# x49_dash.net
KiCad netlist of a schematic drawn in EAGLE
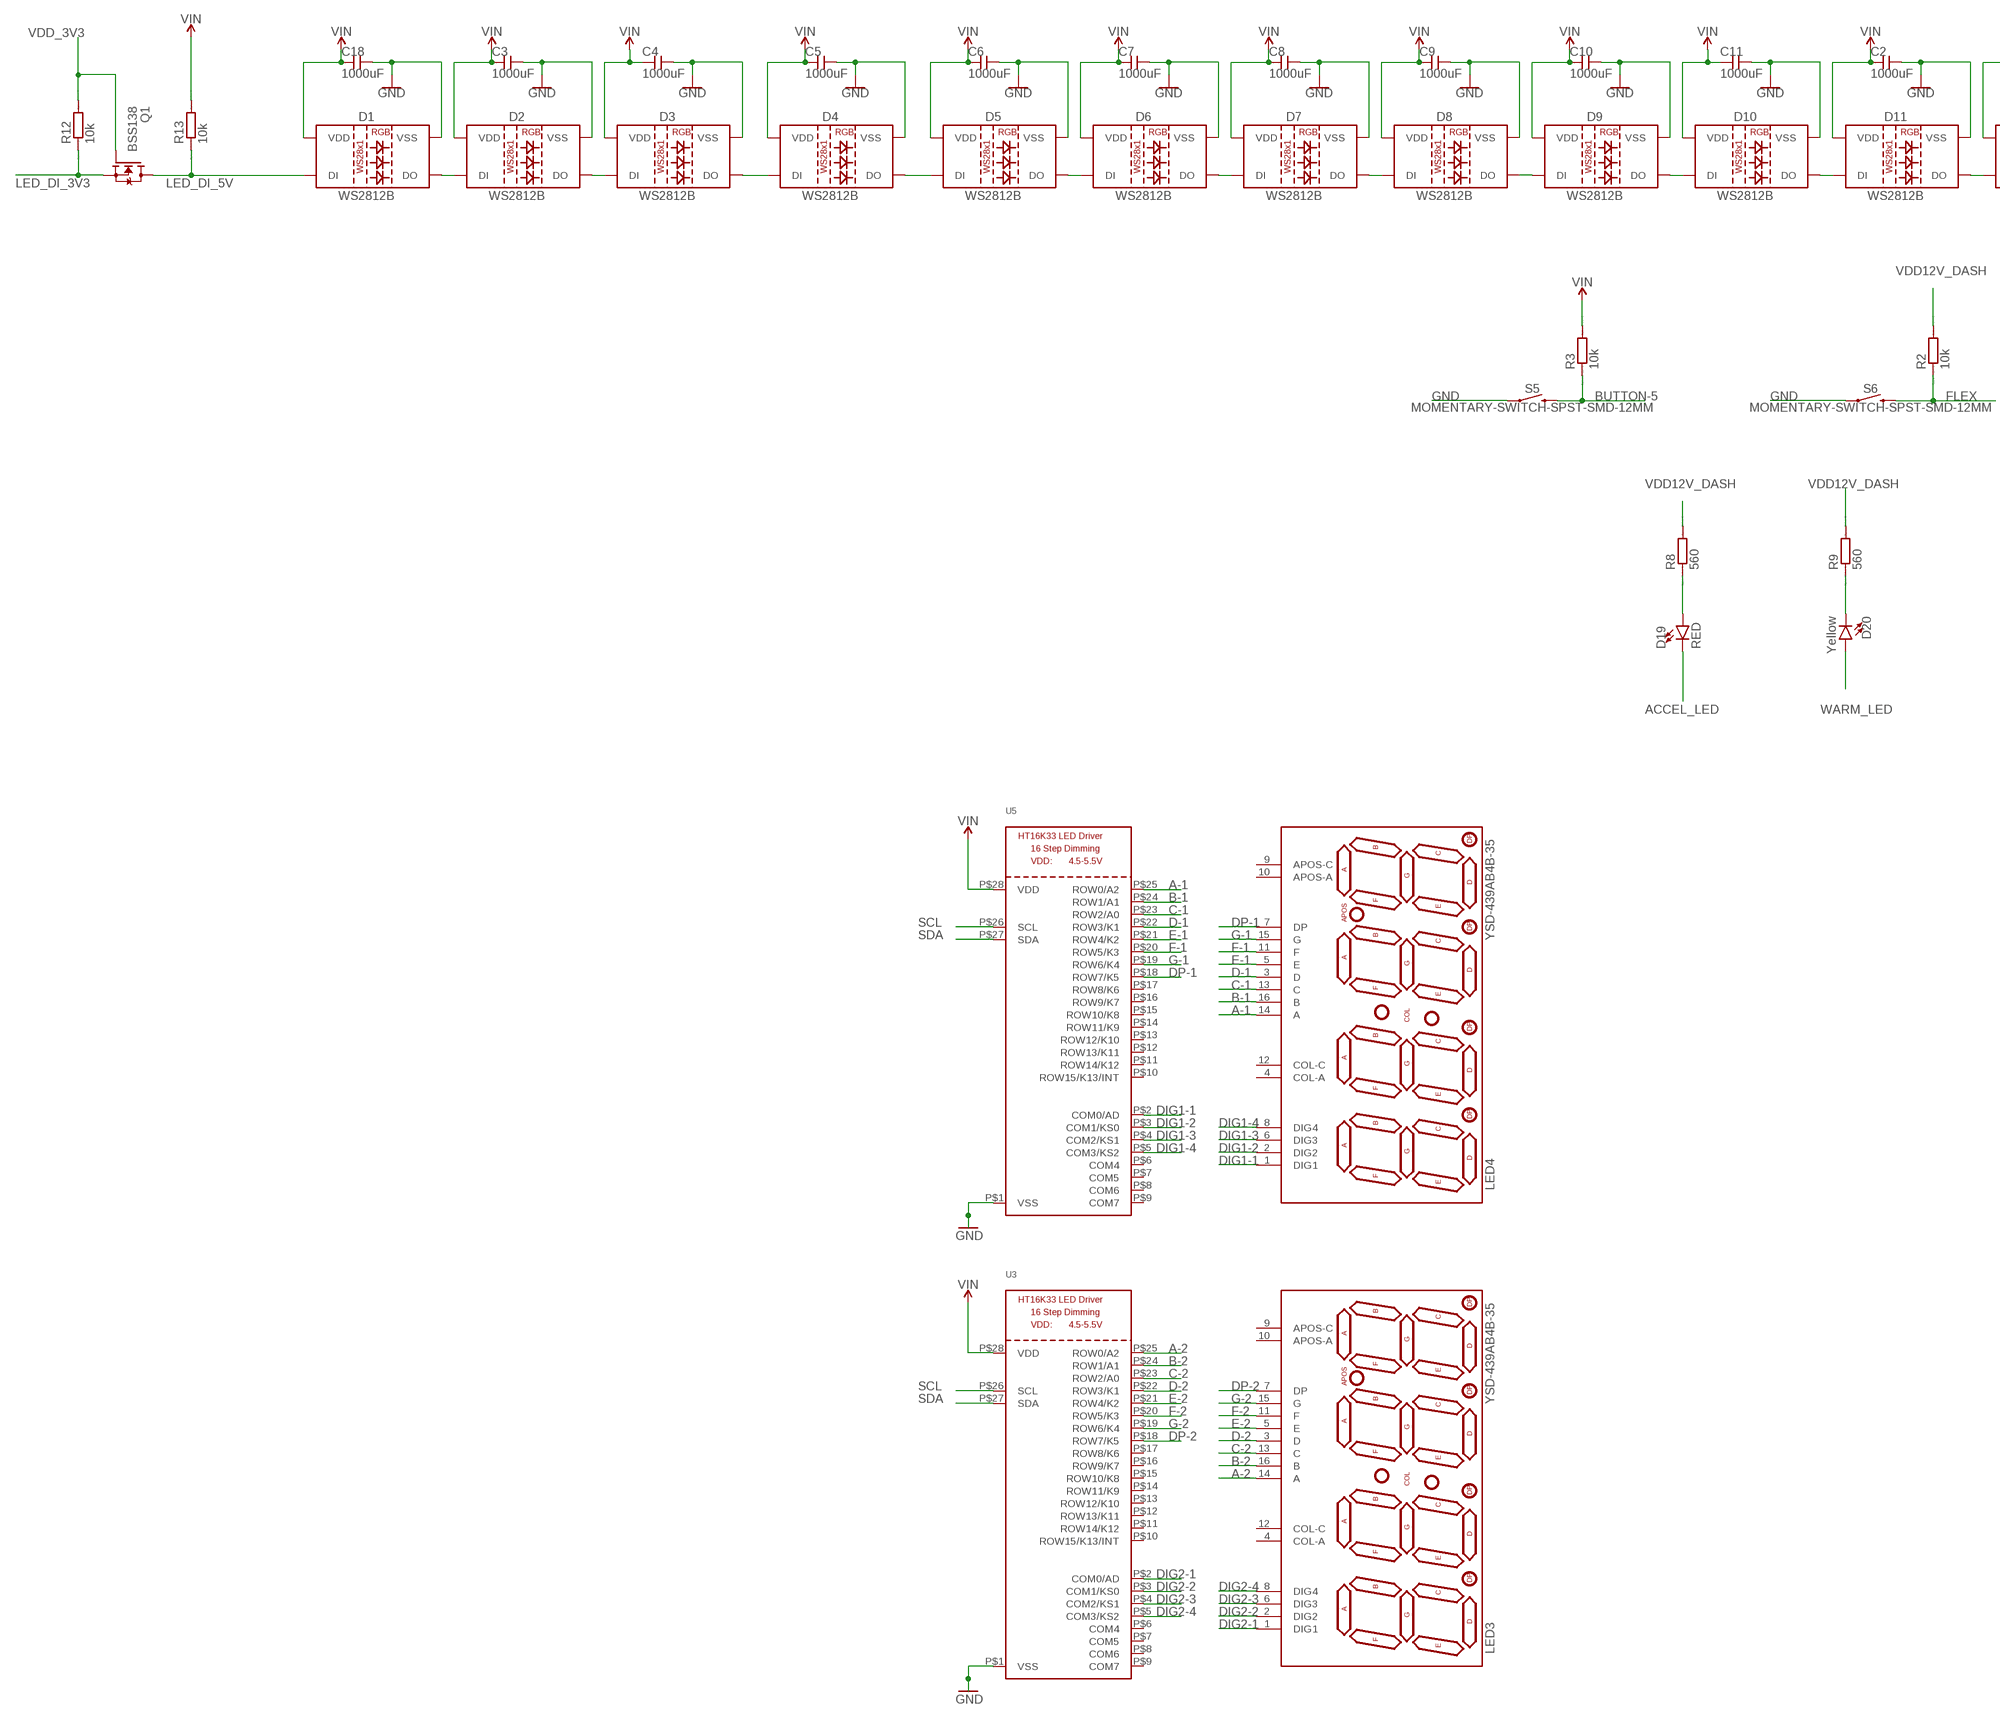
[diagram p0: schematic, sheet 1, part 1 of 2]
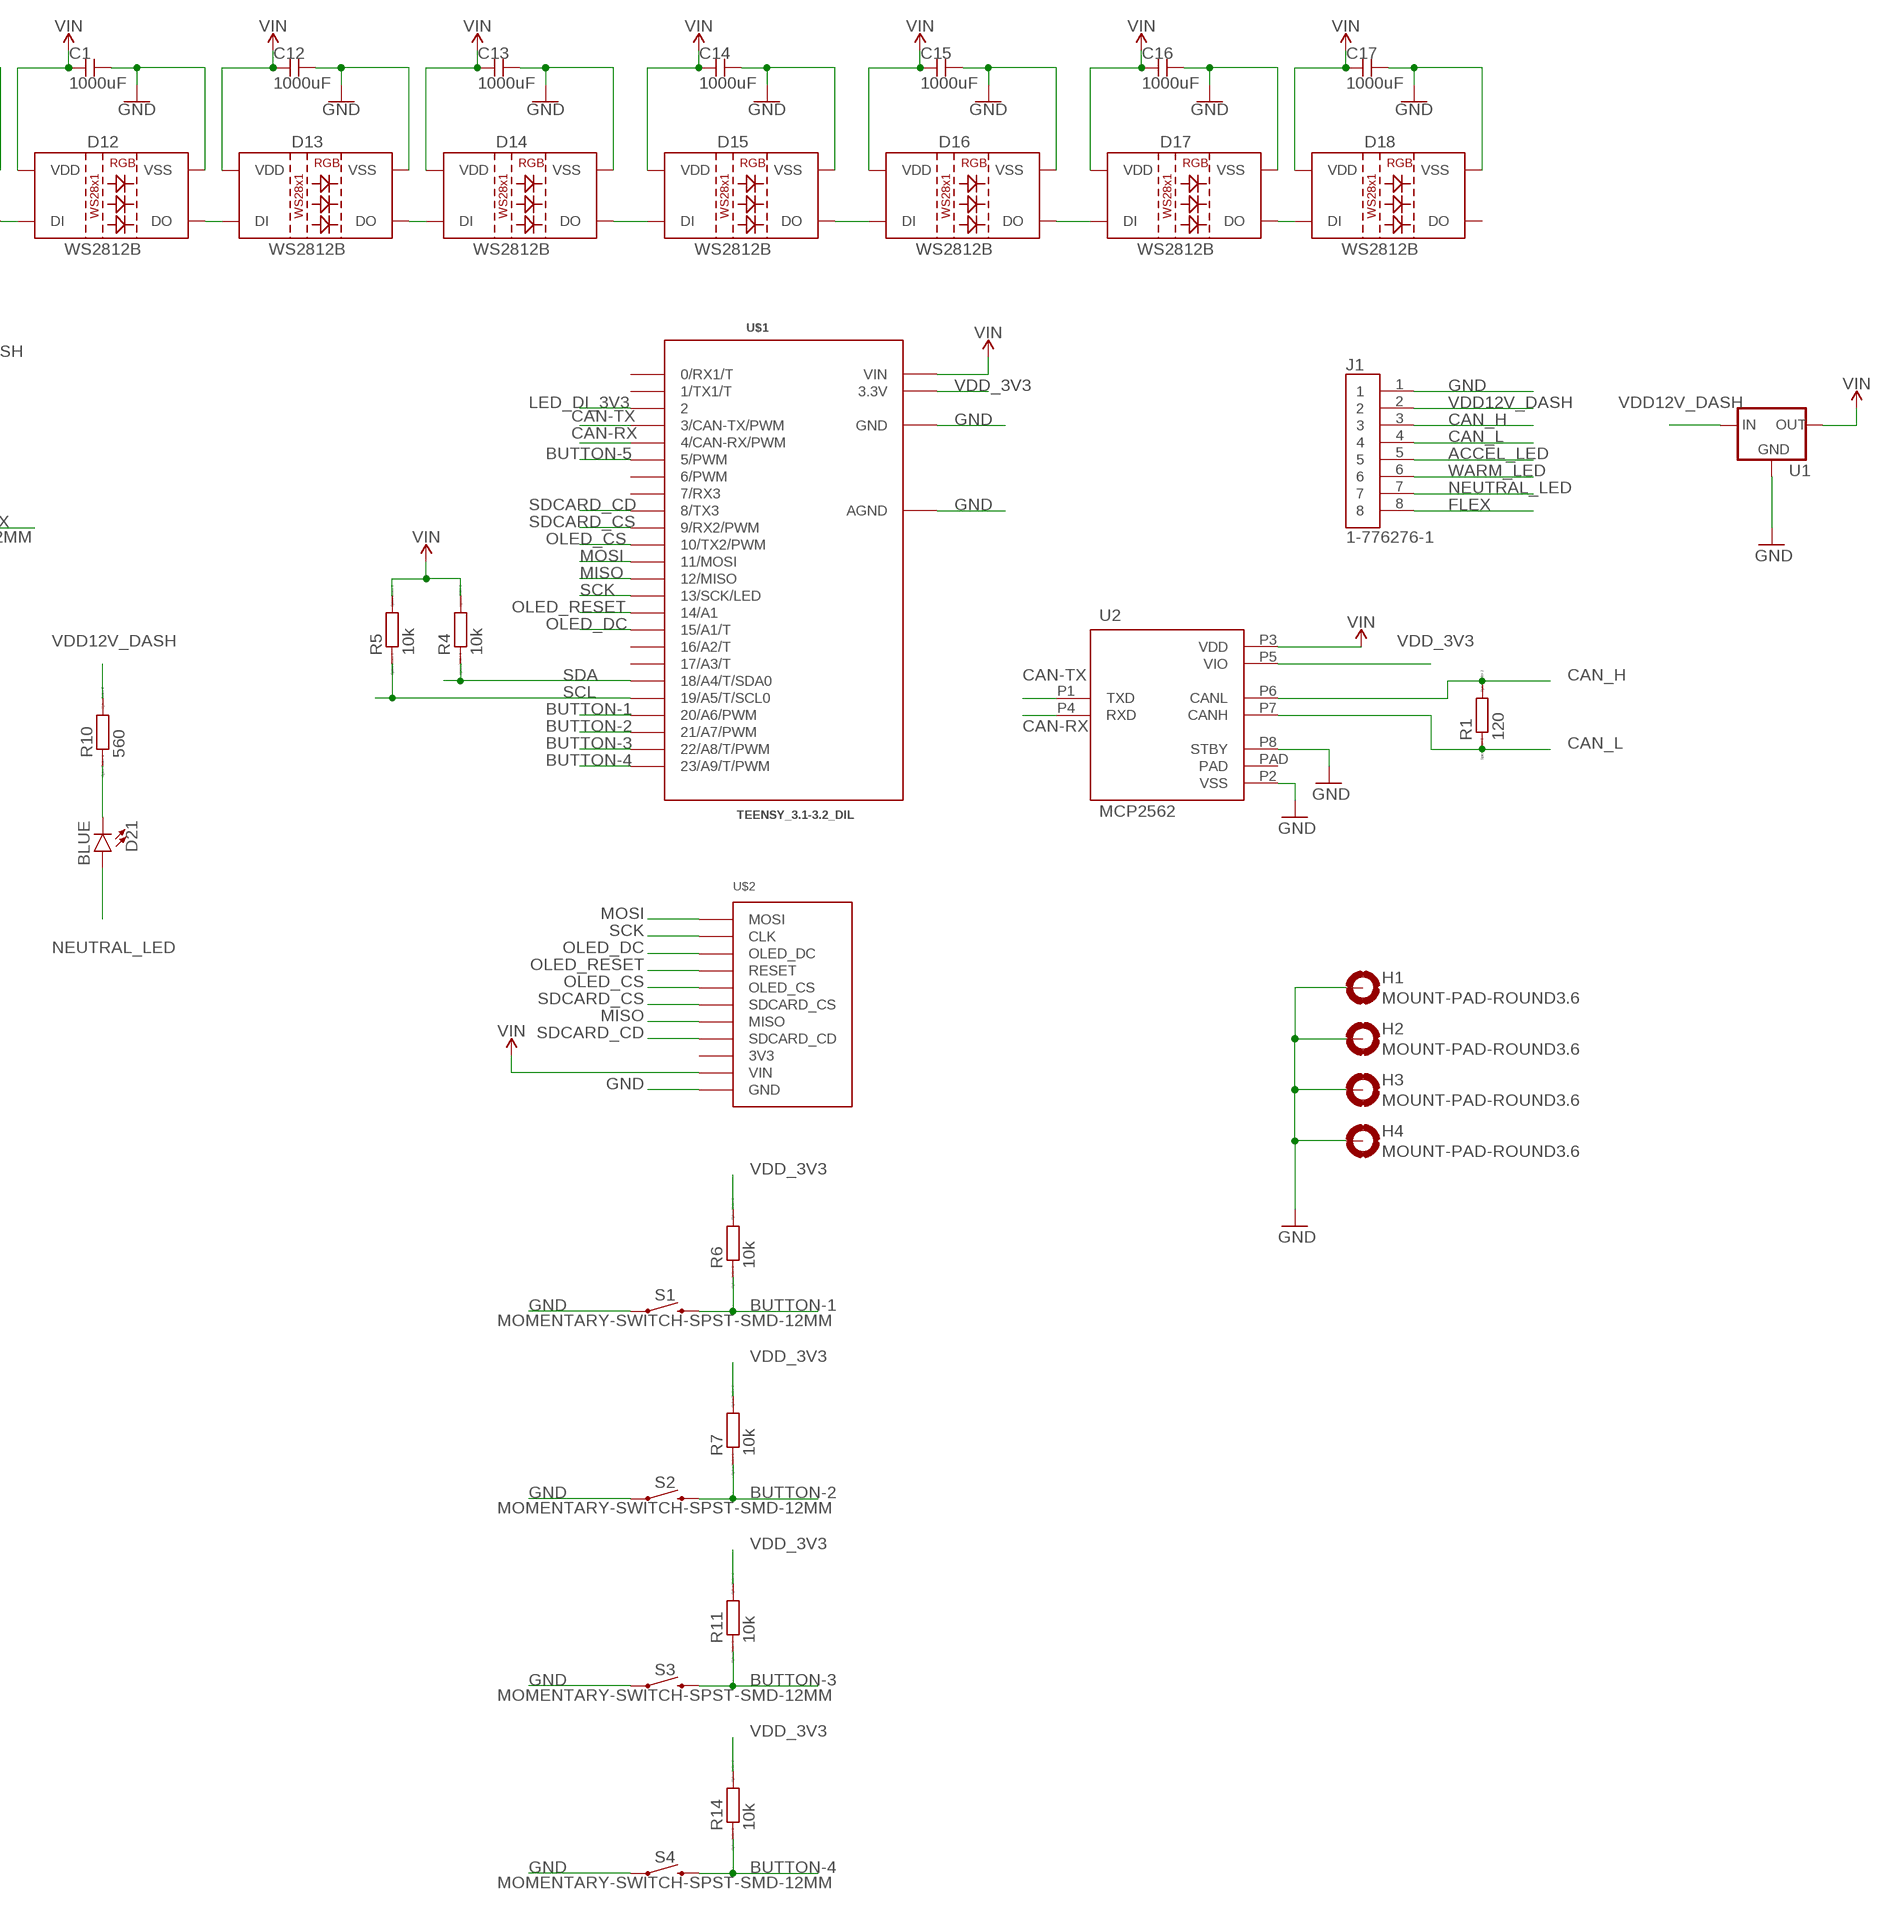
[diagram p1: schematic, sheet 1, part 2 of 2]

(export (version "E")
  (design (tool "Eeschema 10.0.6"))
  (components
    (comp (ref "C1")
      (value "1000uF")
      (footprint "eagle-import:1005")
      (libsource (lib "eagle-import") (part "CAP-1005"))
    )
    (comp (ref "C2")
      (value "1000uF")
      (footprint "eagle-import:1005")
      (libsource (lib "eagle-import") (part "CAP-1005"))
    )
    (comp (ref "C3")
      (value "1000uF")
      (footprint "eagle-import:1005")
      (libsource (lib "eagle-import") (part "CAP-1005"))
    )
    (comp (ref "C4")
      (value "1000uF")
      (footprint "eagle-import:1005")
      (libsource (lib "eagle-import") (part "CAP-1005"))
    )
    (comp (ref "C5")
      (value "1000uF")
      (footprint "eagle-import:1005")
      (libsource (lib "eagle-import") (part "CAP-1005"))
    )
    (comp (ref "C6")
      (value "1000uF")
      (footprint "eagle-import:1005")
      (libsource (lib "eagle-import") (part "CAP-1005"))
    )
    (comp (ref "C7")
      (value "1000uF")
      (footprint "eagle-import:1005")
      (libsource (lib "eagle-import") (part "CAP-1005"))
    )
    (comp (ref "C8")
      (value "1000uF")
      (footprint "eagle-import:1005")
      (libsource (lib "eagle-import") (part "CAP-1005"))
    )
    (comp (ref "C9")
      (value "1000uF")
      (footprint "eagle-import:1005")
      (libsource (lib "eagle-import") (part "CAP-1005"))
    )
    (comp (ref "C10")
      (value "1000uF")
      (footprint "eagle-import:1005")
      (libsource (lib "eagle-import") (part "CAP-1005"))
    )
    (comp (ref "C11")
      (value "1000uF")
      (footprint "eagle-import:1005")
      (libsource (lib "eagle-import") (part "CAP-1005"))
    )
    (comp (ref "C12")
      (value "1000uF")
      (footprint "eagle-import:1005")
      (libsource (lib "eagle-import") (part "CAP-1005"))
    )
    (comp (ref "C13")
      (value "1000uF")
      (footprint "eagle-import:1005")
      (libsource (lib "eagle-import") (part "CAP-1005"))
    )
    (comp (ref "C14")
      (value "1000uF")
      (footprint "eagle-import:1005")
      (libsource (lib "eagle-import") (part "CAP-1005"))
    )
    (comp (ref "C15")
      (value "1000uF")
      (footprint "eagle-import:1005")
      (libsource (lib "eagle-import") (part "CAP-1005"))
    )
    (comp (ref "C16")
      (value "1000uF")
      (footprint "eagle-import:1005")
      (libsource (lib "eagle-import") (part "CAP-1005"))
    )
    (comp (ref "C17")
      (value "1000uF")
      (footprint "eagle-import:1005")
      (libsource (lib "eagle-import") (part "CAP-1005"))
    )
    (comp (ref "C18")
      (value "1000uF")
      (footprint "eagle-import:1005")
      (libsource (lib "eagle-import") (part "CAP-1005"))
    )
    (comp (ref "D1")
      (value "WS2812B")
      (footprint "eagle-import:WS2812B")
      (libsource (lib "eagle-import") (part "WS2812B"))
    )
    (comp (ref "D2")
      (value "WS2812B")
      (footprint "eagle-import:WS2812B")
      (libsource (lib "eagle-import") (part "WS2812B"))
    )
    (comp (ref "D3")
      (value "WS2812B")
      (footprint "eagle-import:WS2812B")
      (libsource (lib "eagle-import") (part "WS2812B"))
    )
    (comp (ref "D4")
      (value "WS2812B")
      (footprint "eagle-import:WS2812B")
      (libsource (lib "eagle-import") (part "WS2812B"))
    )
    (comp (ref "D5")
      (value "WS2812B")
      (footprint "eagle-import:WS2812B")
      (libsource (lib "eagle-import") (part "WS2812B"))
    )
    (comp (ref "D6")
      (value "WS2812B")
      (footprint "eagle-import:WS2812B")
      (libsource (lib "eagle-import") (part "WS2812B"))
    )
    (comp (ref "D7")
      (value "WS2812B")
      (footprint "eagle-import:WS2812B")
      (libsource (lib "eagle-import") (part "WS2812B"))
    )
    (comp (ref "D8")
      (value "WS2812B")
      (footprint "eagle-import:WS2812B")
      (libsource (lib "eagle-import") (part "WS2812B"))
    )
    (comp (ref "D9")
      (value "WS2812B")
      (footprint "eagle-import:WS2812B")
      (libsource (lib "eagle-import") (part "WS2812B"))
    )
    (comp (ref "D10")
      (value "WS2812B")
      (footprint "eagle-import:WS2812B")
      (libsource (lib "eagle-import") (part "WS2812B"))
    )
    (comp (ref "D11")
      (value "WS2812B")
      (footprint "eagle-import:WS2812B")
      (libsource (lib "eagle-import") (part "WS2812B"))
    )
    (comp (ref "D12")
      (value "WS2812B")
      (footprint "eagle-import:WS2812B")
      (libsource (lib "eagle-import") (part "WS2812B"))
    )
    (comp (ref "D13")
      (value "WS2812B")
      (footprint "eagle-import:WS2812B")
      (libsource (lib "eagle-import") (part "WS2812B"))
    )
    (comp (ref "D14")
      (value "WS2812B")
      (footprint "eagle-import:WS2812B")
      (libsource (lib "eagle-import") (part "WS2812B"))
    )
    (comp (ref "D15")
      (value "WS2812B")
      (footprint "eagle-import:WS2812B")
      (libsource (lib "eagle-import") (part "WS2812B"))
    )
    (comp (ref "D16")
      (value "WS2812B")
      (footprint "eagle-import:WS2812B")
      (libsource (lib "eagle-import") (part "WS2812B"))
    )
    (comp (ref "D17")
      (value "WS2812B")
      (footprint "eagle-import:WS2812B")
      (libsource (lib "eagle-import") (part "WS2812B"))
    )
    (comp (ref "D18")
      (value "WS2812B")
      (footprint "eagle-import:WS2812B")
      (libsource (lib "eagle-import") (part "WS2812B"))
    )
    (comp (ref "D19")
      (value "RED")
      (footprint "eagle-import:LED-0603")
      (libsource (lib "eagle-import") (part "LED-RED0603"))
    )
    (comp (ref "D20")
      (value "Yellow")
      (footprint "eagle-import:LED-0603")
      (libsource (lib "eagle-import") (part "LED-YELLOW0603"))
    )
    (comp (ref "D21")
      (value "BLUE")
      (footprint "eagle-import:LED-0603")
      (libsource (lib "eagle-import") (part "LED-BLUE0603"))
    )
    (comp (ref "H1")
      (value "MOUNT-PAD-ROUND3.6")
      (footprint "eagle-import:3,6-PAD")
      (libsource (lib "eagle-import") (part "MOUNT-PAD-ROUND3.6"))
    )
    (comp (ref "H2")
      (value "MOUNT-PAD-ROUND3.6")
      (footprint "eagle-import:3,6-PAD")
      (libsource (lib "eagle-import") (part "MOUNT-PAD-ROUND3.6"))
    )
    (comp (ref "H3")
      (value "MOUNT-PAD-ROUND3.6")
      (footprint "eagle-import:3,6-PAD")
      (libsource (lib "eagle-import") (part "MOUNT-PAD-ROUND3.6"))
    )
    (comp (ref "H4")
      (value "MOUNT-PAD-ROUND3.6")
      (footprint "eagle-import:3,6-PAD")
      (libsource (lib "eagle-import") (part "MOUNT-PAD-ROUND3.6"))
    )
    (comp (ref "J1")
      (value "1-776276-1")
      (footprint "eagle-import:TE_1-776276-1")
      (fields (field (name "MANUFACTURER") "TE Connectivity"))
      (libsource (lib "eagle-import") (part "1-776276-1"))
    )
    (comp (ref "LED3")
      (value "YSD-439AB4B-35")
      (footprint "eagle-import:7-SEGMENT-4DIGIT-YOUNGSUN")
      (libsource (lib "eagle-import") (part "7-SEGMENT-4DIGIT-10MM-BLUE"))
    )
    (comp (ref "LED4")
      (value "YSD-439AB4B-35")
      (footprint "eagle-import:7-SEGMENT-4DIGIT-YOUNGSUN")
      (libsource (lib "eagle-import") (part "7-SEGMENT-4DIGIT-10MM-BLUE"))
    )
    (comp (ref "Q1")
      (value "BSS138")
      (footprint "eagle-import:SOT23")
      (fields (field (name "MF") "Fairchild"))
      (libsource (lib "eagle-import") (part "BSS138"))
    )
    (comp (ref "R1")
      (value "120")
      (footprint "eagle-import:R0805")
      (libsource (lib "eagle-import") (part "R"))
    )
    (comp (ref "R2")
      (value "10k")
      (footprint "eagle-import:R0805")
      (libsource (lib "eagle-import") (part "R"))
    )
    (comp (ref "R3")
      (value "10k")
      (footprint "eagle-import:R0805")
      (libsource (lib "eagle-import") (part "R"))
    )
    (comp (ref "R4")
      (value "10k")
      (footprint "eagle-import:R0805")
      (libsource (lib "eagle-import") (part "R"))
    )
    (comp (ref "R5")
      (value "10k")
      (footprint "eagle-import:R0805")
      (libsource (lib "eagle-import") (part "R"))
    )
    (comp (ref "R6")
      (value "10k")
      (footprint "eagle-import:R0805")
      (libsource (lib "eagle-import") (part "R"))
    )
    (comp (ref "R7")
      (value "10k")
      (footprint "eagle-import:R0805")
      (libsource (lib "eagle-import") (part "R"))
    )
    (comp (ref "R8")
      (value "560")
      (footprint "eagle-import:R0805")
      (libsource (lib "eagle-import") (part "R"))
    )
    (comp (ref "R9")
      (value "560")
      (footprint "eagle-import:R0805")
      (libsource (lib "eagle-import") (part "R"))
    )
    (comp (ref "R10")
      (value "560")
      (footprint "eagle-import:R0805")
      (libsource (lib "eagle-import") (part "R"))
    )
    (comp (ref "R11")
      (value "10k")
      (footprint "eagle-import:R0805")
      (libsource (lib "eagle-import") (part "R"))
    )
    (comp (ref "R12")
      (value "10k")
      (footprint "eagle-import:R0805")
      (libsource (lib "eagle-import") (part "R"))
    )
    (comp (ref "R13")
      (value "10k")
      (footprint "eagle-import:R0805")
      (libsource (lib "eagle-import") (part "R"))
    )
    (comp (ref "R14")
      (value "10k")
      (footprint "eagle-import:R0805")
      (libsource (lib "eagle-import") (part "R"))
    )
    (comp (ref "S1")
      (value "MOMENTARY-SWITCH-SPST-SMD-12MM")
      (footprint "eagle-import:TACTILE_SWITCH_SMD_12MM")
      (libsource (lib "eagle-import") (part "MOMENTARY-SWITCH-SPST-SMD-12MM"))
    )
    (comp (ref "S2")
      (value "MOMENTARY-SWITCH-SPST-SMD-12MM")
      (footprint "eagle-import:TACTILE_SWITCH_SMD_12MM")
      (libsource (lib "eagle-import") (part "MOMENTARY-SWITCH-SPST-SMD-12MM"))
    )
    (comp (ref "S3")
      (value "MOMENTARY-SWITCH-SPST-SMD-12MM")
      (footprint "eagle-import:TACTILE_SWITCH_SMD_12MM")
      (libsource (lib "eagle-import") (part "MOMENTARY-SWITCH-SPST-SMD-12MM"))
    )
    (comp (ref "S4")
      (value "MOMENTARY-SWITCH-SPST-SMD-12MM")
      (footprint "eagle-import:TACTILE_SWITCH_SMD_12MM")
      (libsource (lib "eagle-import") (part "MOMENTARY-SWITCH-SPST-SMD-12MM"))
    )
    (comp (ref "S5")
      (value "MOMENTARY-SWITCH-SPST-SMD-12MM")
      (footprint "eagle-import:TACTILE_SWITCH_SMD_12MM")
      (libsource (lib "eagle-import") (part "MOMENTARY-SWITCH-SPST-SMD-12MM"))
    )
    (comp (ref "S6")
      (value "MOMENTARY-SWITCH-SPST-SMD-12MM")
      (footprint "eagle-import:TACTILE_SWITCH_SMD_12MM")
      (libsource (lib "eagle-import") (part "MOMENTARY-SWITCH-SPST-SMD-12MM"))
    )
    (comp (ref "U$1")
      (value "TEENSY_3.1-3.2_DIL")
      (footprint "eagle-import:TEENSY_3.0-3.2&LC_DIL")
      (libsource (lib "eagle-import") (part "TEENSY_3.1-3.2_DIL"))
    )
    (comp (ref "U$2")
      (value "ADAFRUIT-OLED-BREAKOUT")
      (footprint "eagle-import:OLED-1.27INCH-BREAKOUT")
      (libsource (lib "eagle-import") (part "ADAFRUIT-OLED-BREAKOUT"))
    )
    (comp (ref "U1")
      (value "+12v")
      (footprint "eagle-import:TO-252")
      (libsource (lib "eagle-import") (part "V_REG_78XX7812"))
    )
    (comp (ref "U2")
      (value "MCP2562")
      (footprint "eagle-import:DFN3X3")
      (libsource (lib "eagle-import") (part "MCP2562"))
    )
    (comp (ref "U3")
      (value "HT16K33_SOP28")
      (footprint "eagle-import:SOP28_300MIL")
      (libsource (lib "eagle-import") (part "HT16K33_SOP28"))
    )
    (comp (ref "U5")
      (value "HT16K33_SOP28")
      (footprint "eagle-import:SOP28_300MIL")
      (libsource (lib "eagle-import") (part "HT16K33_SOP28"))
    )
  )
  (nets
    (net (code "1") (name "/3V3") (class "Default")
      (node (ref "U$2") (pin "9") (pinfunction "3V3_9") (pintype "power_in"))
    )
    (net (code "2") (name "/A-1") (class "Default")
      (node (ref "LED4") (pin "14") (pinfunction "A_14") (pintype "bidirectional"))
      (node (ref "U5") (pin "P$25") (pinfunction "ROW0/A2_P$25") (pintype "bidirectional"))
    )
    (net (code "3") (name "/A-2") (class "Default")
      (node (ref "LED3") (pin "14") (pinfunction "A_14") (pintype "bidirectional"))
      (node (ref "U3") (pin "P$25") (pinfunction "ROW0/A2_P$25") (pintype "bidirectional"))
    )
    (net (code "4") (name "/ACCEL_LED") (class "Default")
      (node (ref "D19") (pin "C") (pinfunction "C_C") (pintype "passive"))
      (node (ref "J1") (pin "5") (pinfunction "5_5") (pintype "passive"))
    )
    (net (code "5") (name "/B-1") (class "Default")
      (node (ref "LED4") (pin "16") (pinfunction "B_16") (pintype "bidirectional"))
      (node (ref "U5") (pin "P$24") (pinfunction "ROW1/A1_P$24") (pintype "bidirectional"))
    )
    (net (code "6") (name "/B-2") (class "Default")
      (node (ref "LED3") (pin "16") (pinfunction "B_16") (pintype "bidirectional"))
      (node (ref "U3") (pin "P$24") (pinfunction "ROW1/A1_P$24") (pintype "bidirectional"))
    )
    (net (code "7") (name "/BUTTON-1") (class "Default")
      (node (ref "R6") (pin "1") (pinfunction "1_1") (pintype "passive"))
      (node (ref "S1") (pin "3") (pinfunction "2_3") (pintype "passive"))
      (node (ref "U$1") (pin "20/A6") (pinfunction "20/A6/PWM_20/A6") (pintype "bidirectional"))
    )
    (net (code "8") (name "/BUTTON-2") (class "Default")
      (node (ref "R7") (pin "1") (pinfunction "1_1") (pintype "passive"))
      (node (ref "S2") (pin "3") (pinfunction "2_3") (pintype "passive"))
      (node (ref "U$1") (pin "21/A7") (pinfunction "21/A7/PWM_21/A7") (pintype "bidirectional"))
    )
    (net (code "9") (name "/BUTTON-3") (class "Default")
      (node (ref "R11") (pin "1") (pinfunction "1_1") (pintype "passive"))
      (node (ref "S3") (pin "3") (pinfunction "2_3") (pintype "passive"))
      (node (ref "U$1") (pin "22/A8") (pinfunction "22/A8/T/PWM_22/A8") (pintype "bidirectional"))
    )
    (net (code "10") (name "/BUTTON-4") (class "Default")
      (node (ref "R14") (pin "1") (pinfunction "1_1") (pintype "passive"))
      (node (ref "S4") (pin "3") (pinfunction "2_3") (pintype "passive"))
      (node (ref "U$1") (pin "23/A9") (pinfunction "23/A9/T/PWM_23/A9") (pintype "bidirectional"))
    )
    (net (code "11") (name "/BUTTON-5") (class "Default")
      (node (ref "R3") (pin "1") (pinfunction "1_1") (pintype "passive"))
      (node (ref "S5") (pin "3") (pinfunction "2_3") (pintype "passive"))
      (node (ref "U$1") (pin "5") (pinfunction "5/PWM_5") (pintype "bidirectional"))
    )
    (net (code "12") (name "/C-1") (class "Default")
      (node (ref "LED4") (pin "13") (pinfunction "C_13") (pintype "bidirectional"))
      (node (ref "U5") (pin "P$23") (pinfunction "ROW2/A0_P$23") (pintype "bidirectional"))
    )
    (net (code "13") (name "/C-2") (class "Default")
      (node (ref "LED3") (pin "13") (pinfunction "C_13") (pintype "bidirectional"))
      (node (ref "U3") (pin "P$23") (pinfunction "ROW2/A0_P$23") (pintype "bidirectional"))
    )
    (net (code "14") (name "/CAN-RX") (class "Default")
      (node (ref "U$1") (pin "4") (pinfunction "4/CAN-RX/PWM_4") (pintype "bidirectional"))
      (node (ref "U2") (pin "P4") (pinfunction "RXD_P4") (pintype "bidirectional"))
    )
    (net (code "15") (name "/CAN-TX") (class "Default")
      (node (ref "U$1") (pin "3") (pinfunction "3/CAN-TX/PWM_3") (pintype "bidirectional"))
      (node (ref "U2") (pin "P1") (pinfunction "TXD_P1") (pintype "bidirectional"))
    )
    (net (code "16") (name "/CAN_H") (class "Default")
      (node (ref "J1") (pin "3") (pinfunction "3_3") (pintype "passive"))
      (node (ref "R1") (pin "2") (pinfunction "2_2") (pintype "passive"))
      (node (ref "U2") (pin "P6") (pinfunction "CANL_P6") (pintype "bidirectional"))
    )
    (net (code "17") (name "/CAN_L") (class "Default")
      (node (ref "J1") (pin "4") (pinfunction "4_4") (pintype "passive"))
      (node (ref "R1") (pin "1") (pinfunction "1_1") (pintype "passive"))
      (node (ref "U2") (pin "P7") (pinfunction "CANH_P7") (pintype "bidirectional"))
    )
    (net (code "18") (name "/D-1") (class "Default")
      (node (ref "LED4") (pin "3") (pinfunction "D_3") (pintype "bidirectional"))
      (node (ref "U5") (pin "P$22") (pinfunction "ROW3/K1_P$22") (pintype "bidirectional"))
    )
    (net (code "19") (name "/D-2") (class "Default")
      (node (ref "LED3") (pin "3") (pinfunction "D_3") (pintype "bidirectional"))
      (node (ref "U3") (pin "P$22") (pinfunction "ROW3/K1_P$22") (pintype "bidirectional"))
    )
    (net (code "20") (name "/DIG1-1") (class "Default")
      (node (ref "LED4") (pin "1") (pinfunction "DIG1_1") (pintype "bidirectional"))
      (node (ref "U5") (pin "P$2") (pinfunction "COM0/AD_P$2") (pintype "bidirectional"))
    )
    (net (code "21") (name "/DIG1-2") (class "Default")
      (node (ref "LED4") (pin "2") (pinfunction "DIG2_2") (pintype "bidirectional"))
      (node (ref "U5") (pin "P$3") (pinfunction "COM1/KS0_P$3") (pintype "bidirectional"))
    )
    (net (code "22") (name "/DIG1-3") (class "Default")
      (node (ref "LED4") (pin "6") (pinfunction "DIG3_6") (pintype "bidirectional"))
      (node (ref "U5") (pin "P$4") (pinfunction "COM2/KS1_P$4") (pintype "bidirectional"))
    )
    (net (code "23") (name "/DIG1-4") (class "Default")
      (node (ref "LED4") (pin "8") (pinfunction "DIG4_8") (pintype "bidirectional"))
      (node (ref "U5") (pin "P$5") (pinfunction "COM3/KS2_P$5") (pintype "bidirectional"))
    )
    (net (code "24") (name "/DIG2-1") (class "Default")
      (node (ref "LED3") (pin "1") (pinfunction "DIG1_1") (pintype "bidirectional"))
      (node (ref "U3") (pin "P$2") (pinfunction "COM0/AD_P$2") (pintype "bidirectional"))
    )
    (net (code "25") (name "/DIG2-2") (class "Default")
      (node (ref "LED3") (pin "2") (pinfunction "DIG2_2") (pintype "bidirectional"))
      (node (ref "U3") (pin "P$3") (pinfunction "COM1/KS0_P$3") (pintype "bidirectional"))
    )
    (net (code "26") (name "/DIG2-3") (class "Default")
      (node (ref "LED3") (pin "6") (pinfunction "DIG3_6") (pintype "bidirectional"))
      (node (ref "U3") (pin "P$4") (pinfunction "COM2/KS1_P$4") (pintype "bidirectional"))
    )
    (net (code "27") (name "/DIG2-4") (class "Default")
      (node (ref "LED3") (pin "8") (pinfunction "DIG4_8") (pintype "bidirectional"))
      (node (ref "U3") (pin "P$5") (pinfunction "COM3/KS2_P$5") (pintype "bidirectional"))
    )
    (net (code "28") (name "/DP-1") (class "Default")
      (node (ref "LED4") (pin "7") (pinfunction "DP_7") (pintype "bidirectional"))
      (node (ref "U5") (pin "P$18") (pinfunction "ROW7/K5_P$18") (pintype "bidirectional"))
    )
    (net (code "29") (name "/DP-2") (class "Default")
      (node (ref "LED3") (pin "7") (pinfunction "DP_7") (pintype "bidirectional"))
      (node (ref "U3") (pin "P$18") (pinfunction "ROW7/K5_P$18") (pintype "bidirectional"))
    )
    (net (code "30") (name "/E-1") (class "Default")
      (node (ref "LED4") (pin "5") (pinfunction "E_5") (pintype "bidirectional"))
      (node (ref "U5") (pin "P$21") (pinfunction "ROW4/K2_P$21") (pintype "bidirectional"))
    )
    (net (code "31") (name "/E-2") (class "Default")
      (node (ref "LED3") (pin "5") (pinfunction "E_5") (pintype "bidirectional"))
      (node (ref "U3") (pin "P$21") (pinfunction "ROW4/K2_P$21") (pintype "bidirectional"))
    )
    (net (code "32") (name "/F-1") (class "Default")
      (node (ref "LED4") (pin "11") (pinfunction "F_11") (pintype "bidirectional"))
      (node (ref "U5") (pin "P$20") (pinfunction "ROW5/K3_P$20") (pintype "bidirectional"))
    )
    (net (code "33") (name "/F-2") (class "Default")
      (node (ref "LED3") (pin "11") (pinfunction "F_11") (pintype "bidirectional"))
      (node (ref "U3") (pin "P$20") (pinfunction "ROW5/K3_P$20") (pintype "bidirectional"))
    )
    (net (code "34") (name "/FLEX") (class "Default")
      (node (ref "J1") (pin "8") (pinfunction "8_8") (pintype "passive"))
      (node (ref "R2") (pin "1") (pinfunction "1_1") (pintype "passive"))
      (node (ref "S6") (pin "3") (pinfunction "2_3") (pintype "passive"))
    )
    (net (code "35") (name "/G-1") (class "Default")
      (node (ref "LED4") (pin "15") (pinfunction "G_15") (pintype "bidirectional"))
      (node (ref "U5") (pin "P$19") (pinfunction "ROW6/K4_P$19") (pintype "bidirectional"))
    )
    (net (code "36") (name "/G-2") (class "Default")
      (node (ref "LED3") (pin "15") (pinfunction "G_15") (pintype "bidirectional"))
      (node (ref "U3") (pin "P$19") (pinfunction "ROW6/K4_P$19") (pintype "bidirectional"))
    )
    (net (code "37") (name "/LED_DI_3V3") (class "Default")
      (node (ref "Q1") (pin "2") (pinfunction "S_2") (pintype "passive"))
      (node (ref "R12") (pin "1") (pinfunction "1_1") (pintype "passive"))
      (node (ref "U$1") (pin "2") (pinfunction "2_2") (pintype "bidirectional"))
    )
    (net (code "38") (name "/LED_DI_5V") (class "Default")
      (node (ref "D1") (pin "4") (pinfunction "DI_4") (pintype "bidirectional"))
      (node (ref "Q1") (pin "3") (pinfunction "D_3") (pintype "passive"))
      (node (ref "R13") (pin "1") (pinfunction "1_1") (pintype "passive"))
    )
    (net (code "39") (name "/MISO") (class "Default")
      (node (ref "U$1") (pin "12") (pinfunction "12/MISO_12") (pintype "bidirectional"))
      (node (ref "U$2") (pin "7") (pinfunction "MISO_7") (pintype "bidirectional"))
    )
    (net (code "40") (name "/MOSI") (class "Default")
      (node (ref "U$1") (pin "11") (pinfunction "11/MOSI_11") (pintype "bidirectional"))
      (node (ref "U$2") (pin "1") (pinfunction "MOSI_1") (pintype "bidirectional"))
    )
    (net (code "41") (name "/NEUTRAL_LED") (class "Default")
      (node (ref "D21") (pin "A") (pinfunction "A_A") (pintype "passive"))
      (node (ref "J1") (pin "7") (pinfunction "7_7") (pintype "passive"))
    )
    (net (code "42") (name "/OLED_CS") (class "Default")
      (node (ref "U$1") (pin "10") (pinfunction "10/TX2/PWM_10") (pintype "bidirectional"))
      (node (ref "U$2") (pin "5") (pinfunction "OLED_CS_5") (pintype "bidirectional"))
    )
    (net (code "43") (name "/OLED_DC") (class "Default")
      (node (ref "U$1") (pin "15/A1") (pinfunction "15/A1/T_15/A1") (pintype "bidirectional"))
      (node (ref "U$2") (pin "3") (pinfunction "OLED_DC_3") (pintype "bidirectional"))
    )
    (net (code "44") (name "/OLED_RESET") (class "Default")
      (node (ref "U$1") (pin "14/A0") (pinfunction "14/A1_14/A0") (pintype "bidirectional"))
      (node (ref "U$2") (pin "4") (pinfunction "RESET_4") (pintype "bidirectional"))
    )
    (net (code "45") (name "/SCK") (class "Default")
      (node (ref "U$1") (pin "13") (pinfunction "13/SCK/LED_13") (pintype "bidirectional"))
      (node (ref "U$2") (pin "2") (pinfunction "CLK_2") (pintype "bidirectional"))
    )
    (net (code "46") (name "/SCL") (class "Default")
      (node (ref "R5") (pin "1") (pinfunction "1_1") (pintype "passive"))
      (node (ref "U$1") (pin "19/A5") (pinfunction "19/A5/T/SCL0_19/A5") (pintype "bidirectional"))
      (node (ref "U3") (pin "P$26") (pinfunction "SCL_P$26") (pintype "bidirectional"))
      (node (ref "U5") (pin "P$26") (pinfunction "SCL_P$26") (pintype "bidirectional"))
    )
    (net (code "47") (name "/SDA") (class "Default")
      (node (ref "R4") (pin "1") (pinfunction "1_1") (pintype "passive"))
      (node (ref "U$1") (pin "18/A4") (pinfunction "18/A4/T/SDA0_18/A4") (pintype "bidirectional"))
      (node (ref "U3") (pin "P$27") (pinfunction "SDA_P$27") (pintype "bidirectional"))
      (node (ref "U5") (pin "P$27") (pinfunction "SDA_P$27") (pintype "bidirectional"))
    )
    (net (code "48") (name "/SDCARD_CD") (class "Default")
      (node (ref "U$1") (pin "8") (pinfunction "8/TX3_8") (pintype "bidirectional"))
      (node (ref "U$2") (pin "8") (pinfunction "SDCARD_CD_8") (pintype "bidirectional"))
    )
    (net (code "49") (name "/SDCARD_CS") (class "Default")
      (node (ref "U$1") (pin "9") (pinfunction "9/RX2/PWM_9") (pintype "bidirectional"))
      (node (ref "U$2") (pin "6") (pinfunction "SDCARD_CS_6") (pintype "bidirectional"))
    )
    (net (code "50") (name "/VDD12V_DASH") (class "Default")
      (node (ref "J1") (pin "2") (pinfunction "2_2") (pintype "passive"))
      (node (ref "R10") (pin "2") (pinfunction "2_2") (pintype "passive"))
      (node (ref "R2") (pin "2") (pinfunction "2_2") (pintype "passive"))
      (node (ref "R8") (pin "2") (pinfunction "2_2") (pintype "passive"))
      (node (ref "R9") (pin "2") (pinfunction "2_2") (pintype "passive"))
      (node (ref "U1") (pin "1") (pinfunction "IN_1") (pintype "input"))
    )
    (net (code "51") (name "/VDD_3V3") (class "Default")
      (node (ref "Q1") (pin "1") (pinfunction "G_1") (pintype "passive"))
      (node (ref "R11") (pin "2") (pinfunction "2_2") (pintype "passive"))
      (node (ref "R12") (pin "2") (pinfunction "2_2") (pintype "passive"))
      (node (ref "R14") (pin "2") (pinfunction "2_2") (pintype "passive"))
      (node (ref "R6") (pin "2") (pinfunction "2_2") (pintype "passive"))
      (node (ref "R7") (pin "2") (pinfunction "2_2") (pintype "passive"))
      (node (ref "U$1") (pin "3.3V") (pinfunction "3.3V_3.3V") (pintype "power_in"))
      (node (ref "U2") (pin "P5") (pinfunction "VIO_P5") (pintype "bidirectional"))
    )
    (net (code "52") (name "/WARM_LED") (class "Default")
      (node (ref "D20") (pin "A") (pinfunction "A_A") (pintype "passive"))
      (node (ref "J1") (pin "6") (pinfunction "6_6") (pintype "passive"))
    )
    (net (code "53") (name "GND") (class "Default")
      (node (ref "C1") (pin "P$2") (pinfunction "2_P$2") (pintype "passive"))
      (node (ref "C10") (pin "P$2") (pinfunction "2_P$2") (pintype "passive"))
      (node (ref "C11") (pin "P$2") (pinfunction "2_P$2") (pintype "passive"))
      (node (ref "C12") (pin "P$2") (pinfunction "2_P$2") (pintype "passive"))
      (node (ref "C13") (pin "P$2") (pinfunction "2_P$2") (pintype "passive"))
      (node (ref "C14") (pin "P$2") (pinfunction "2_P$2") (pintype "passive"))
      (node (ref "C15") (pin "P$2") (pinfunction "2_P$2") (pintype "passive"))
      (node (ref "C16") (pin "P$2") (pinfunction "2_P$2") (pintype "passive"))
      (node (ref "C17") (pin "P$2") (pinfunction "2_P$2") (pintype "passive"))
      (node (ref "C18") (pin "P$2") (pinfunction "2_P$2") (pintype "passive"))
      (node (ref "C2") (pin "P$2") (pinfunction "2_P$2") (pintype "passive"))
      (node (ref "C3") (pin "P$2") (pinfunction "2_P$2") (pintype "passive"))
      (node (ref "C4") (pin "P$2") (pinfunction "2_P$2") (pintype "passive"))
      (node (ref "C5") (pin "P$2") (pinfunction "2_P$2") (pintype "passive"))
      (node (ref "C6") (pin "P$2") (pinfunction "2_P$2") (pintype "passive"))
      (node (ref "C7") (pin "P$2") (pinfunction "2_P$2") (pintype "passive"))
      (node (ref "C8") (pin "P$2") (pinfunction "2_P$2") (pintype "passive"))
      (node (ref "C9") (pin "P$2") (pinfunction "2_P$2") (pintype "passive"))
      (node (ref "D1") (pin "3") (pinfunction "VSS_3") (pintype "bidirectional"))
      (node (ref "D10") (pin "3") (pinfunction "VSS_3") (pintype "bidirectional"))
      (node (ref "D11") (pin "3") (pinfunction "VSS_3") (pintype "bidirectional"))
      (node (ref "D12") (pin "3") (pinfunction "VSS_3") (pintype "bidirectional"))
      (node (ref "D13") (pin "3") (pinfunction "VSS_3") (pintype "bidirectional"))
      (node (ref "D14") (pin "3") (pinfunction "VSS_3") (pintype "bidirectional"))
      (node (ref "D15") (pin "3") (pinfunction "VSS_3") (pintype "bidirectional"))
      (node (ref "D16") (pin "3") (pinfunction "VSS_3") (pintype "bidirectional"))
      (node (ref "D17") (pin "3") (pinfunction "VSS_3") (pintype "bidirectional"))
      (node (ref "D18") (pin "3") (pinfunction "VSS_3") (pintype "bidirectional"))
      (node (ref "D2") (pin "3") (pinfunction "VSS_3") (pintype "bidirectional"))
      (node (ref "D3") (pin "3") (pinfunction "VSS_3") (pintype "bidirectional"))
      (node (ref "D4") (pin "3") (pinfunction "VSS_3") (pintype "bidirectional"))
      (node (ref "D5") (pin "3") (pinfunction "VSS_3") (pintype "bidirectional"))
      (node (ref "D6") (pin "3") (pinfunction "VSS_3") (pintype "bidirectional"))
      (node (ref "D7") (pin "3") (pinfunction "VSS_3") (pintype "bidirectional"))
      (node (ref "D8") (pin "3") (pinfunction "VSS_3") (pintype "bidirectional"))
      (node (ref "D9") (pin "3") (pinfunction "VSS_3") (pintype "bidirectional"))
      (node (ref "H1") (pin "B3,6") (pinfunction "MOUNT_B3,6") (pintype "passive"))
      (node (ref "H2") (pin "B3,6") (pinfunction "MOUNT_B3,6") (pintype "passive"))
      (node (ref "H3") (pin "B3,6") (pinfunction "MOUNT_B3,6") (pintype "passive"))
      (node (ref "H4") (pin "B3,6") (pinfunction "MOUNT_B3,6") (pintype "passive"))
      (node (ref "J1") (pin "1") (pinfunction "1_1") (pintype "passive"))
      (node (ref "S1") (pin "1") (pinfunction "1_1") (pintype "passive"))
      (node (ref "S2") (pin "1") (pinfunction "1_1") (pintype "passive"))
      (node (ref "S3") (pin "1") (pinfunction "1_1") (pintype "passive"))
      (node (ref "S4") (pin "1") (pinfunction "1_1") (pintype "passive"))
      (node (ref "S5") (pin "1") (pinfunction "1_1") (pintype "passive"))
      (node (ref "S6") (pin "1") (pinfunction "1_1") (pintype "passive"))
      (node (ref "U$1") (pin "AGND") (pinfunction "AGND_AGND") (pintype "power_in"))
      (node (ref "U$1") (pin "GND") (pinfunction "GND_GND") (pintype "power_in"))
      (node (ref "U$2") (pin "11") (pinfunction "GND_11") (pintype "power_in"))
      (node (ref "U$2") (pin "P$1") (pinfunction "GND_P$1") (pintype "power_in"))
      (node (ref "U$2") (pin "P$2") (pinfunction "GND_P$2") (pintype "power_in"))
      (node (ref "U$2") (pin "P$3") (pinfunction "GND_P$3") (pintype "power_in"))
      (node (ref "U$2") (pin "P$4") (pinfunction "GND_P$4") (pintype "power_in"))
      (node (ref "U1") (pin "3") (pinfunction "GND_3") (pintype "input"))
      (node (ref "U2") (pin "P2") (pinfunction "VSS_P2") (pintype "bidirectional"))
      (node (ref "U2") (pin "P8") (pinfunction "STBY_P8") (pintype "bidirectional"))
      (node (ref "U3") (pin "P$1") (pinfunction "VSS_P$1") (pintype "bidirectional"))
      (node (ref "U5") (pin "P$1") (pinfunction "VSS_P$1") (pintype "bidirectional"))
    )
    (net (code "54") (name "Net-(D1-DO)") (class "Default")
      (node (ref "D1") (pin "2") (pinfunction "DO_2") (pintype "bidirectional"))
      (node (ref "D2") (pin "4") (pinfunction "DI_4") (pintype "bidirectional"))
    )
    (net (code "55") (name "Net-(D2-DO)") (class "Default")
      (node (ref "D2") (pin "2") (pinfunction "DO_2") (pintype "bidirectional"))
      (node (ref "D3") (pin "4") (pinfunction "DI_4") (pintype "bidirectional"))
    )
    (net (code "56") (name "Net-(D3-DO)") (class "Default")
      (node (ref "D3") (pin "2") (pinfunction "DO_2") (pintype "bidirectional"))
      (node (ref "D4") (pin "4") (pinfunction "DI_4") (pintype "bidirectional"))
    )
    (net (code "57") (name "Net-(D4-DO)") (class "Default")
      (node (ref "D4") (pin "2") (pinfunction "DO_2") (pintype "bidirectional"))
      (node (ref "D5") (pin "4") (pinfunction "DI_4") (pintype "bidirectional"))
    )
    (net (code "58") (name "Net-(D5-DO)") (class "Default")
      (node (ref "D5") (pin "2") (pinfunction "DO_2") (pintype "bidirectional"))
      (node (ref "D6") (pin "4") (pinfunction "DI_4") (pintype "bidirectional"))
    )
    (net (code "59") (name "Net-(D6-DO)") (class "Default")
      (node (ref "D6") (pin "2") (pinfunction "DO_2") (pintype "bidirectional"))
      (node (ref "D7") (pin "4") (pinfunction "DI_4") (pintype "bidirectional"))
    )
    (net (code "60") (name "Net-(D7-DO)") (class "Default")
      (node (ref "D7") (pin "2") (pinfunction "DO_2") (pintype "bidirectional"))
      (node (ref "D8") (pin "4") (pinfunction "DI_4") (pintype "bidirectional"))
    )
    (net (code "61") (name "Net-(D8-DO)") (class "Default")
      (node (ref "D8") (pin "2") (pinfunction "DO_2") (pintype "bidirectional"))
      (node (ref "D9") (pin "4") (pinfunction "DI_4") (pintype "bidirectional"))
    )
    (net (code "62") (name "Net-(D10-DI)") (class "Default")
      (node (ref "D10") (pin "4") (pinfunction "DI_4") (pintype "bidirectional"))
      (node (ref "D9") (pin "2") (pinfunction "DO_2") (pintype "bidirectional"))
    )
    (net (code "63") (name "Net-(D10-DO)") (class "Default")
      (node (ref "D10") (pin "2") (pinfunction "DO_2") (pintype "bidirectional"))
      (node (ref "D11") (pin "4") (pinfunction "DI_4") (pintype "bidirectional"))
    )
    (net (code "64") (name "Net-(D11-DO)") (class "Default")
      (node (ref "D11") (pin "2") (pinfunction "DO_2") (pintype "bidirectional"))
      (node (ref "D12") (pin "4") (pinfunction "DI_4") (pintype "bidirectional"))
    )
    (net (code "65") (name "Net-(D12-DO)") (class "Default")
      (node (ref "D12") (pin "2") (pinfunction "DO_2") (pintype "bidirectional"))
      (node (ref "D13") (pin "4") (pinfunction "DI_4") (pintype "bidirectional"))
    )
    (net (code "66") (name "Net-(D13-DO)") (class "Default")
      (node (ref "D13") (pin "2") (pinfunction "DO_2") (pintype "bidirectional"))
      (node (ref "D14") (pin "4") (pinfunction "DI_4") (pintype "bidirectional"))
    )
    (net (code "67") (name "Net-(D14-DO)") (class "Default")
      (node (ref "D14") (pin "2") (pinfunction "DO_2") (pintype "bidirectional"))
      (node (ref "D15") (pin "4") (pinfunction "DI_4") (pintype "bidirectional"))
    )
    (net (code "68") (name "Net-(D15-DO)") (class "Default")
      (node (ref "D15") (pin "2") (pinfunction "DO_2") (pintype "bidirectional"))
      (node (ref "D16") (pin "4") (pinfunction "DI_4") (pintype "bidirectional"))
    )
    (net (code "69") (name "Net-(D16-DO)") (class "Default")
      (node (ref "D16") (pin "2") (pinfunction "DO_2") (pintype "bidirectional"))
      (node (ref "D17") (pin "4") (pinfunction "DI_4") (pintype "bidirectional"))
    )
    (net (code "70") (name "Net-(D17-DO)") (class "Default")
      (node (ref "D17") (pin "2") (pinfunction "DO_2") (pintype "bidirectional"))
      (node (ref "D18") (pin "4") (pinfunction "DI_4") (pintype "bidirectional"))
    )
    (net (code "71") (name "Net-(D19-PadA)") (class "Default")
      (node (ref "D19") (pin "A") (pinfunction "A_A") (pintype "passive"))
      (node (ref "R8") (pin "1") (pinfunction "1_1") (pintype "passive"))
    )
    (net (code "72") (name "Net-(D20-PadC)") (class "Default")
      (node (ref "D20") (pin "C") (pinfunction "C_C") (pintype "passive"))
      (node (ref "R9") (pin "1") (pinfunction "1_1") (pintype "passive"))
    )
    (net (code "73") (name "Net-(D21-PadC)") (class "Default")
      (node (ref "D21") (pin "C") (pinfunction "C_C") (pintype "passive"))
      (node (ref "R10") (pin "1") (pinfunction "1_1") (pintype "passive"))
    )
    (net (code "74") (name "VIN") (class "Default")
      (node (ref "C1") (pin "P$1") (pinfunction "1_P$1") (pintype "passive"))
      (node (ref "C10") (pin "P$1") (pinfunction "1_P$1") (pintype "passive"))
      (node (ref "C11") (pin "P$1") (pinfunction "1_P$1") (pintype "passive"))
      (node (ref "C12") (pin "P$1") (pinfunction "1_P$1") (pintype "passive"))
      (node (ref "C13") (pin "P$1") (pinfunction "1_P$1") (pintype "passive"))
      (node (ref "C14") (pin "P$1") (pinfunction "1_P$1") (pintype "passive"))
      (node (ref "C15") (pin "P$1") (pinfunction "1_P$1") (pintype "passive"))
      (node (ref "C16") (pin "P$1") (pinfunction "1_P$1") (pintype "passive"))
      (node (ref "C17") (pin "P$1") (pinfunction "1_P$1") (pintype "passive"))
      (node (ref "C18") (pin "P$1") (pinfunction "1_P$1") (pintype "passive"))
      (node (ref "C2") (pin "P$1") (pinfunction "1_P$1") (pintype "passive"))
      (node (ref "C3") (pin "P$1") (pinfunction "1_P$1") (pintype "passive"))
      (node (ref "C4") (pin "P$1") (pinfunction "1_P$1") (pintype "passive"))
      (node (ref "C5") (pin "P$1") (pinfunction "1_P$1") (pintype "passive"))
      (node (ref "C6") (pin "P$1") (pinfunction "1_P$1") (pintype "passive"))
      (node (ref "C7") (pin "P$1") (pinfunction "1_P$1") (pintype "passive"))
      (node (ref "C8") (pin "P$1") (pinfunction "1_P$1") (pintype "passive"))
      (node (ref "C9") (pin "P$1") (pinfunction "1_P$1") (pintype "passive"))
      (node (ref "D1") (pin "1") (pinfunction "VDD_1") (pintype "bidirectional"))
      (node (ref "D10") (pin "1") (pinfunction "VDD_1") (pintype "bidirectional"))
      (node (ref "D11") (pin "1") (pinfunction "VDD_1") (pintype "bidirectional"))
      (node (ref "D12") (pin "1") (pinfunction "VDD_1") (pintype "bidirectional"))
      (node (ref "D13") (pin "1") (pinfunction "VDD_1") (pintype "bidirectional"))
      (node (ref "D14") (pin "1") (pinfunction "VDD_1") (pintype "bidirectional"))
      (node (ref "D15") (pin "1") (pinfunction "VDD_1") (pintype "bidirectional"))
      (node (ref "D16") (pin "1") (pinfunction "VDD_1") (pintype "bidirectional"))
      (node (ref "D17") (pin "1") (pinfunction "VDD_1") (pintype "bidirectional"))
      (node (ref "D18") (pin "1") (pinfunction "VDD_1") (pintype "bidirectional"))
      (node (ref "D2") (pin "1") (pinfunction "VDD_1") (pintype "bidirectional"))
      (node (ref "D3") (pin "1") (pinfunction "VDD_1") (pintype "bidirectional"))
      (node (ref "D4") (pin "1") (pinfunction "VDD_1") (pintype "bidirectional"))
      (node (ref "D5") (pin "1") (pinfunction "VDD_1") (pintype "bidirectional"))
      (node (ref "D6") (pin "1") (pinfunction "VDD_1") (pintype "bidirectional"))
      (node (ref "D7") (pin "1") (pinfunction "VDD_1") (pintype "bidirectional"))
      (node (ref "D8") (pin "1") (pinfunction "VDD_1") (pintype "bidirectional"))
      (node (ref "D9") (pin "1") (pinfunction "VDD_1") (pintype "bidirectional"))
      (node (ref "R13") (pin "2") (pinfunction "2_2") (pintype "passive"))
      (node (ref "R3") (pin "2") (pinfunction "2_2") (pintype "passive"))
      (node (ref "R4") (pin "2") (pinfunction "2_2") (pintype "passive"))
      (node (ref "R5") (pin "2") (pinfunction "2_2") (pintype "passive"))
      (node (ref "U$1") (pin "VIN") (pinfunction "VIN_VIN") (pintype "power_in"))
      (node (ref "U$2") (pin "10") (pinfunction "VIN_10") (pintype "power_in"))
      (node (ref "U1") (pin "2") (pinfunction "OUT_2") (pintype "passive"))
      (node (ref "U2") (pin "P3") (pinfunction "VDD_P3") (pintype "bidirectional"))
      (node (ref "U3") (pin "P$28") (pinfunction "VDD_P$28") (pintype "bidirectional"))
      (node (ref "U5") (pin "P$28") (pinfunction "VDD_P$28") (pintype "bidirectional"))
    )
    (net (code "75") (name "unconnected-(D18-DO-Pad2)") (class "Default")
      (node (ref "D18") (pin "2") (pinfunction "DO_2") (pintype "bidirectional"))
    )
    (net (code "76") (name "unconnected-(LED3-APOS-A-Pad10)") (class "Default")
      (node (ref "LED3") (pin "10") (pinfunction "APOS-A_10") (pintype "bidirectional"))
    )
    (net (code "77") (name "unconnected-(LED3-APOS-C-Pad9)") (class "Default")
      (node (ref "LED3") (pin "9") (pinfunction "APOS-C_9") (pintype "bidirectional"))
    )
    (net (code "78") (name "unconnected-(LED3-COL-A-Pad4)") (class "Default")
      (node (ref "LED3") (pin "4") (pinfunction "COL-A_4") (pintype "bidirectional"))
    )
    (net (code "79") (name "unconnected-(LED3-COL-C-Pad12)") (class "Default")
      (node (ref "LED3") (pin "12") (pinfunction "COL-C_12") (pintype "bidirectional"))
    )
    (net (code "80") (name "unconnected-(LED4-APOS-A-Pad10)") (class "Default")
      (node (ref "LED4") (pin "10") (pinfunction "APOS-A_10") (pintype "bidirectional"))
    )
    (net (code "81") (name "unconnected-(LED4-APOS-C-Pad9)") (class "Default")
      (node (ref "LED4") (pin "9") (pinfunction "APOS-C_9") (pintype "bidirectional"))
    )
    (net (code "82") (name "unconnected-(LED4-COL-A-Pad4)") (class "Default")
      (node (ref "LED4") (pin "4") (pinfunction "COL-A_4") (pintype "bidirectional"))
    )
    (net (code "83") (name "unconnected-(LED4-COL-C-Pad12)") (class "Default")
      (node (ref "LED4") (pin "12") (pinfunction "COL-C_12") (pintype "bidirectional"))
    )
    (net (code "84") (name "unconnected-(U$1-0{slash}RX1{slash}T-Pad0)") (class "Default")
      (node (ref "U$1") (pin "0") (pinfunction "0/RX1/T_0") (pintype "bidirectional"))
    )
    (net (code "85") (name "unconnected-(U$1-1{slash}TX1{slash}T-Pad1)") (class "Default")
      (node (ref "U$1") (pin "1") (pinfunction "1/TX1/T_1") (pintype "bidirectional"))
    )
    (net (code "86") (name "unconnected-(U$1-6{slash}PWM-Pad6)") (class "Default")
      (node (ref "U$1") (pin "6") (pinfunction "6/PWM_6") (pintype "bidirectional"))
    )
    (net (code "87") (name "unconnected-(U$1-7{slash}RX3-Pad7)") (class "Default")
      (node (ref "U$1") (pin "7") (pinfunction "7/RX3_7") (pintype "bidirectional"))
    )
    (net (code "88") (name "unconnected-(U$1-16{slash}A2{slash}T-Pad16{slash}A2)") (class "Default")
      (node (ref "U$1") (pin "16/A2") (pinfunction "16/A2/T_16/A2") (pintype "bidirectional"))
    )
    (net (code "89") (name "unconnected-(U$1-17{slash}A3{slash}T-Pad17{slash}A3)") (class "Default")
      (node (ref "U$1") (pin "17/A3") (pinfunction "17/A3/T_17/A3") (pintype "bidirectional"))
    )
    (net (code "90") (name "unconnected-(U2-PadPAD)") (class "Default")
      (node (ref "U2") (pin "PAD") (pinfunction "PAD_PAD") (pintype "bidirectional"))
    )
    (net (code "91") (name "unconnected-(U3-COM4-PadP$6)") (class "Default")
      (node (ref "U3") (pin "P$6") (pinfunction "COM4_P$6") (pintype "bidirectional"))
    )
    (net (code "92") (name "unconnected-(U3-COM5-PadP$7)") (class "Default")
      (node (ref "U3") (pin "P$7") (pinfunction "COM5_P$7") (pintype "bidirectional"))
    )
    (net (code "93") (name "unconnected-(U3-COM6-PadP$8)") (class "Default")
      (node (ref "U3") (pin "P$8") (pinfunction "COM6_P$8") (pintype "bidirectional"))
    )
    (net (code "94") (name "unconnected-(U3-COM7-PadP$9)") (class "Default")
      (node (ref "U3") (pin "P$9") (pinfunction "COM7_P$9") (pintype "bidirectional"))
    )
    (net (code "95") (name "unconnected-(U3-ROW8{slash}K6-PadP$17)") (class "Default")
      (node (ref "U3") (pin "P$17") (pinfunction "ROW8/K6_P$17") (pintype "bidirectional"))
    )
    (net (code "96") (name "unconnected-(U3-ROW9{slash}K7-PadP$16)") (class "Default")
      (node (ref "U3") (pin "P$16") (pinfunction "ROW9/K7_P$16") (pintype "bidirectional"))
    )
    (net (code "97") (name "unconnected-(U3-ROW10{slash}K8-PadP$15)") (class "Default")
      (node (ref "U3") (pin "P$15") (pinfunction "ROW10/K8_P$15") (pintype "bidirectional"))
    )
    (net (code "98") (name "unconnected-(U3-ROW11{slash}K9-PadP$14)") (class "Default")
      (node (ref "U3") (pin "P$14") (pinfunction "ROW11/K9_P$14") (pintype "bidirectional"))
    )
    (net (code "99") (name "unconnected-(U3-ROW12{slash}K10-PadP$13)") (class "Default")
      (node (ref "U3") (pin "P$13") (pinfunction "ROW12/K10_P$13") (pintype "bidirectional"))
    )
    (net (code "100") (name "unconnected-(U3-ROW13{slash}K11-PadP$12)") (class "Default")
      (node (ref "U3") (pin "P$12") (pinfunction "ROW13/K11_P$12") (pintype "bidirectional"))
    )
    (net (code "101") (name "unconnected-(U3-ROW14{slash}K12-PadP$11)") (class "Default")
      (node (ref "U3") (pin "P$11") (pinfunction "ROW14/K12_P$11") (pintype "bidirectional"))
    )
    (net (code "102") (name "unconnected-(U3-ROW15{slash}K13{slash}INT-PadP$10)") (class "Default")
      (node (ref "U3") (pin "P$10") (pinfunction "ROW15/K13/INT_P$10") (pintype "bidirectional"))
    )
    (net (code "103") (name "unconnected-(U5-COM4-PadP$6)") (class "Default")
      (node (ref "U5") (pin "P$6") (pinfunction "COM4_P$6") (pintype "bidirectional"))
    )
    (net (code "104") (name "unconnected-(U5-COM5-PadP$7)") (class "Default")
      (node (ref "U5") (pin "P$7") (pinfunction "COM5_P$7") (pintype "bidirectional"))
    )
    (net (code "105") (name "unconnected-(U5-COM6-PadP$8)") (class "Default")
      (node (ref "U5") (pin "P$8") (pinfunction "COM6_P$8") (pintype "bidirectional"))
    )
    (net (code "106") (name "unconnected-(U5-COM7-PadP$9)") (class "Default")
      (node (ref "U5") (pin "P$9") (pinfunction "COM7_P$9") (pintype "bidirectional"))
    )
    (net (code "107") (name "unconnected-(U5-ROW8{slash}K6-PadP$17)") (class "Default")
      (node (ref "U5") (pin "P$17") (pinfunction "ROW8/K6_P$17") (pintype "bidirectional"))
    )
    (net (code "108") (name "unconnected-(U5-ROW9{slash}K7-PadP$16)") (class "Default")
      (node (ref "U5") (pin "P$16") (pinfunction "ROW9/K7_P$16") (pintype "bidirectional"))
    )
    (net (code "109") (name "unconnected-(U5-ROW10{slash}K8-PadP$15)") (class "Default")
      (node (ref "U5") (pin "P$15") (pinfunction "ROW10/K8_P$15") (pintype "bidirectional"))
    )
    (net (code "110") (name "unconnected-(U5-ROW11{slash}K9-PadP$14)") (class "Default")
      (node (ref "U5") (pin "P$14") (pinfunction "ROW11/K9_P$14") (pintype "bidirectional"))
    )
    (net (code "111") (name "unconnected-(U5-ROW12{slash}K10-PadP$13)") (class "Default")
      (node (ref "U5") (pin "P$13") (pinfunction "ROW12/K10_P$13") (pintype "bidirectional"))
    )
    (net (code "112") (name "unconnected-(U5-ROW13{slash}K11-PadP$12)") (class "Default")
      (node (ref "U5") (pin "P$12") (pinfunction "ROW13/K11_P$12") (pintype "bidirectional"))
    )
    (net (code "113") (name "unconnected-(U5-ROW14{slash}K12-PadP$11)") (class "Default")
      (node (ref "U5") (pin "P$11") (pinfunction "ROW14/K12_P$11") (pintype "bidirectional"))
    )
    (net (code "114") (name "unconnected-(U5-ROW15{slash}K13{slash}INT-PadP$10)") (class "Default")
      (node (ref "U5") (pin "P$10") (pinfunction "ROW15/K13/INT_P$10") (pintype "bidirectional"))
    )
  )
)
